# brick_i2c_templature.net
KiCad netlist of a schematic drawn in EAGLE
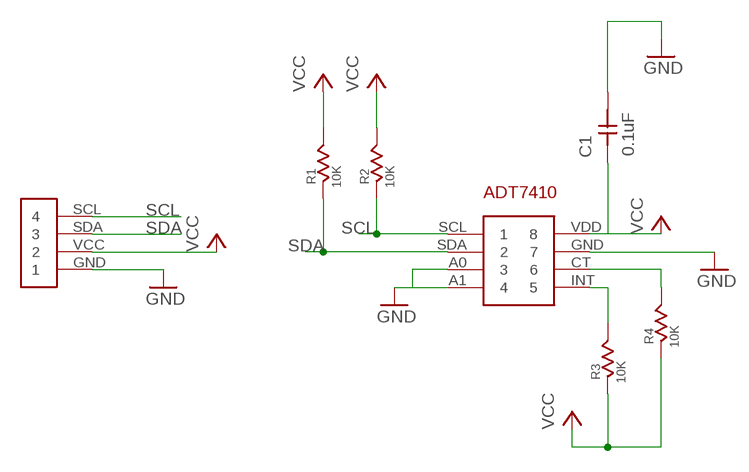
[diagram p0: schematic, sheet 1]

(export (version "E")
  (design (tool "Eeschema 10.0.6"))
  (components
    (comp (ref "C1")
      (value "0.1uF")
      (footprint "eagle-import:RESISTOR_0603")
      (libsource (lib "eagle-import") (part "CAPACITOR_0603"))
    )
    (comp (ref "R1")
      (value "10K")
      (footprint "eagle-import:RESISTOR_0603")
      (libsource (lib "eagle-import") (part "RESISTOR_0603"))
    )
    (comp (ref "R2")
      (value "10K")
      (footprint "eagle-import:RESISTOR_0603")
      (libsource (lib "eagle-import") (part "RESISTOR_0603"))
    )
    (comp (ref "R3")
      (value "10K")
      (footprint "eagle-import:RESISTOR_0603")
      (libsource (lib "eagle-import") (part "RESISTOR_0603"))
    )
    (comp (ref "R4")
      (value "10K")
      (footprint "eagle-import:RESISTOR_0603")
      (libsource (lib "eagle-import") (part "RESISTOR_0603"))
    )
    (comp (ref "U$1")
      (value "I2C-ADT7410")
      (footprint "eagle-import:I2C-ADT7410")
      (libsource (lib "eagle-import") (part "I2C-ADT7410"))
    )
    (comp (ref "U$2")
      (value "BRICK_I2C")
      (footprint "eagle-import:BRICK_I2C")
      (libsource (lib "eagle-import") (part "BRICK_I2C"))
    )
  )
  (nets
    (net (code "1") (name "/SCL") (class "Default")
      (node (ref "R2") (pin "P$1") (pinfunction "1_P$1") (pintype "bidirectional"))
      (node (ref "U$1") (pin "SCL") (pinfunction "1_SCL") (pintype "bidirectional"))
      (node (ref "U$2") (pin "SCL") (pinfunction "4_SCL") (pintype "bidirectional"))
    )
    (net (code "2") (name "/SDA") (class "Default")
      (node (ref "R1") (pin "P$1") (pinfunction "1_P$1") (pintype "bidirectional"))
      (node (ref "U$1") (pin "SDA") (pinfunction "2_SDA") (pintype "bidirectional"))
      (node (ref "U$2") (pin "SDA") (pinfunction "3_SDA") (pintype "bidirectional"))
    )
    (net (code "3") (name "GND") (class "Default")
      (node (ref "C1") (pin "P$2") (pinfunction "P$2_P$2") (pintype "bidirectional"))
      (node (ref "U$1") (pin "A0") (pinfunction "3_A0") (pintype "bidirectional"))
      (node (ref "U$1") (pin "A1") (pinfunction "4_A1") (pintype "bidirectional"))
      (node (ref "U$1") (pin "GND") (pinfunction "7_GND") (pintype "bidirectional"))
      (node (ref "U$2") (pin "GND") (pinfunction "1_GND") (pintype "bidirectional"))
    )
    (net (code "4") (name "Net-(R3-2)") (class "Default")
      (node (ref "R3") (pin "P$2") (pinfunction "2_P$2") (pintype "bidirectional"))
      (node (ref "U$1") (pin "INT") (pinfunction "5_INT") (pintype "bidirectional"))
    )
    (net (code "5") (name "Net-(R4-2)") (class "Default")
      (node (ref "R4") (pin "P$2") (pinfunction "2_P$2") (pintype "bidirectional"))
      (node (ref "U$1") (pin "CT") (pinfunction "6_CT") (pintype "bidirectional"))
    )
    (net (code "6") (name "VCC") (class "Default")
      (node (ref "C1") (pin "P$1") (pinfunction "P$1_P$1") (pintype "bidirectional"))
      (node (ref "R1") (pin "P$2") (pinfunction "2_P$2") (pintype "bidirectional"))
      (node (ref "R2") (pin "P$2") (pinfunction "2_P$2") (pintype "bidirectional"))
      (node (ref "R3") (pin "P$1") (pinfunction "1_P$1") (pintype "bidirectional"))
      (node (ref "R4") (pin "P$1") (pinfunction "1_P$1") (pintype "bidirectional"))
      (node (ref "U$1") (pin "VDD") (pinfunction "8_VDD") (pintype "bidirectional"))
      (node (ref "U$2") (pin "VCC") (pinfunction "2_VCC") (pintype "bidirectional"))
    )
  )
)
